# schody_v1.net
KiCad netlist of a schematic drawn in EAGLE
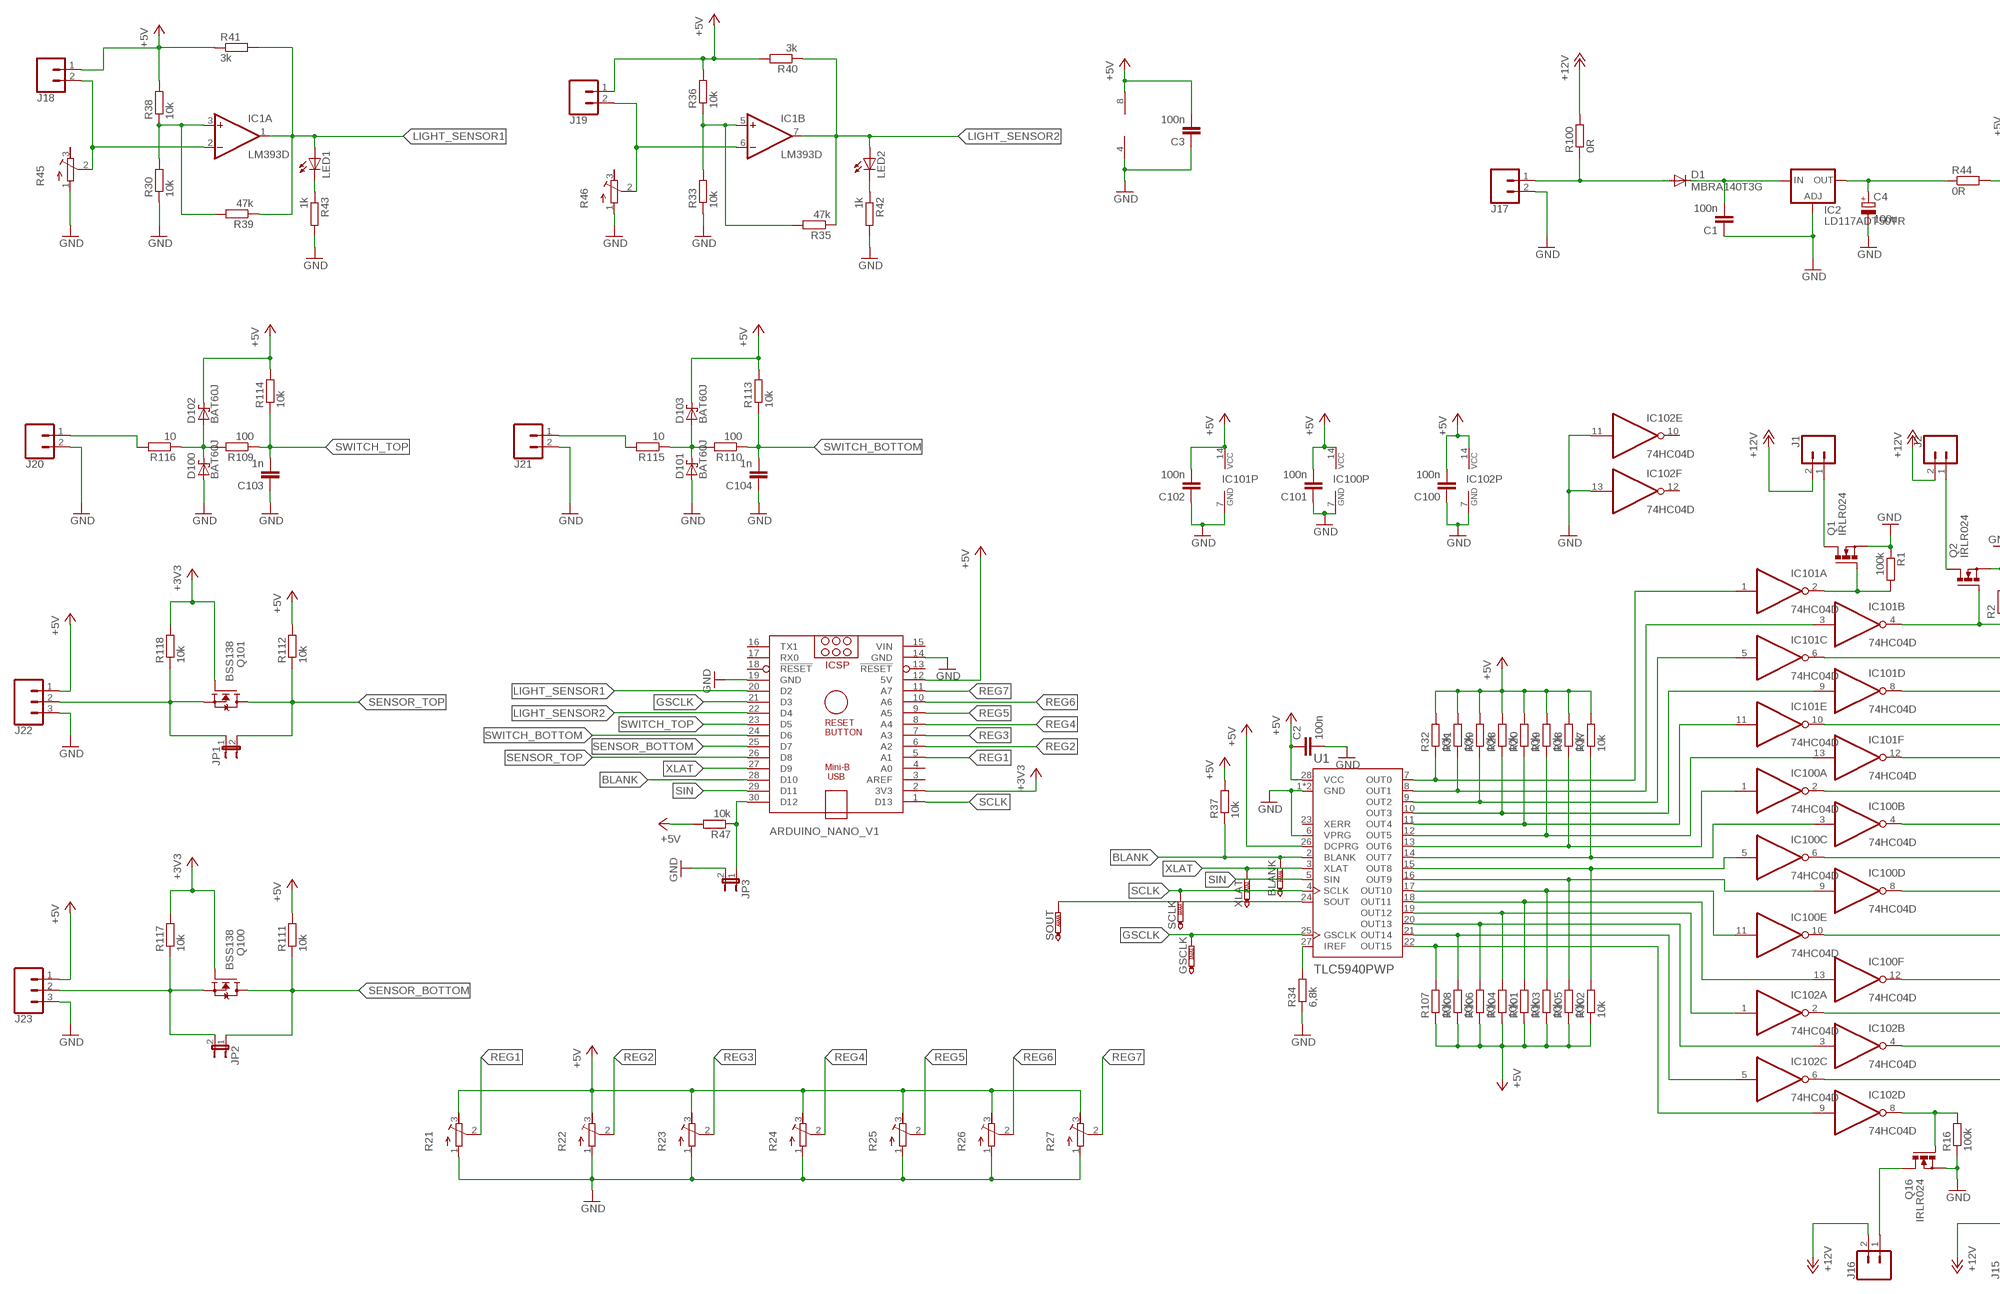
[diagram p0: schematic, sheet 1, part 1 of 2]
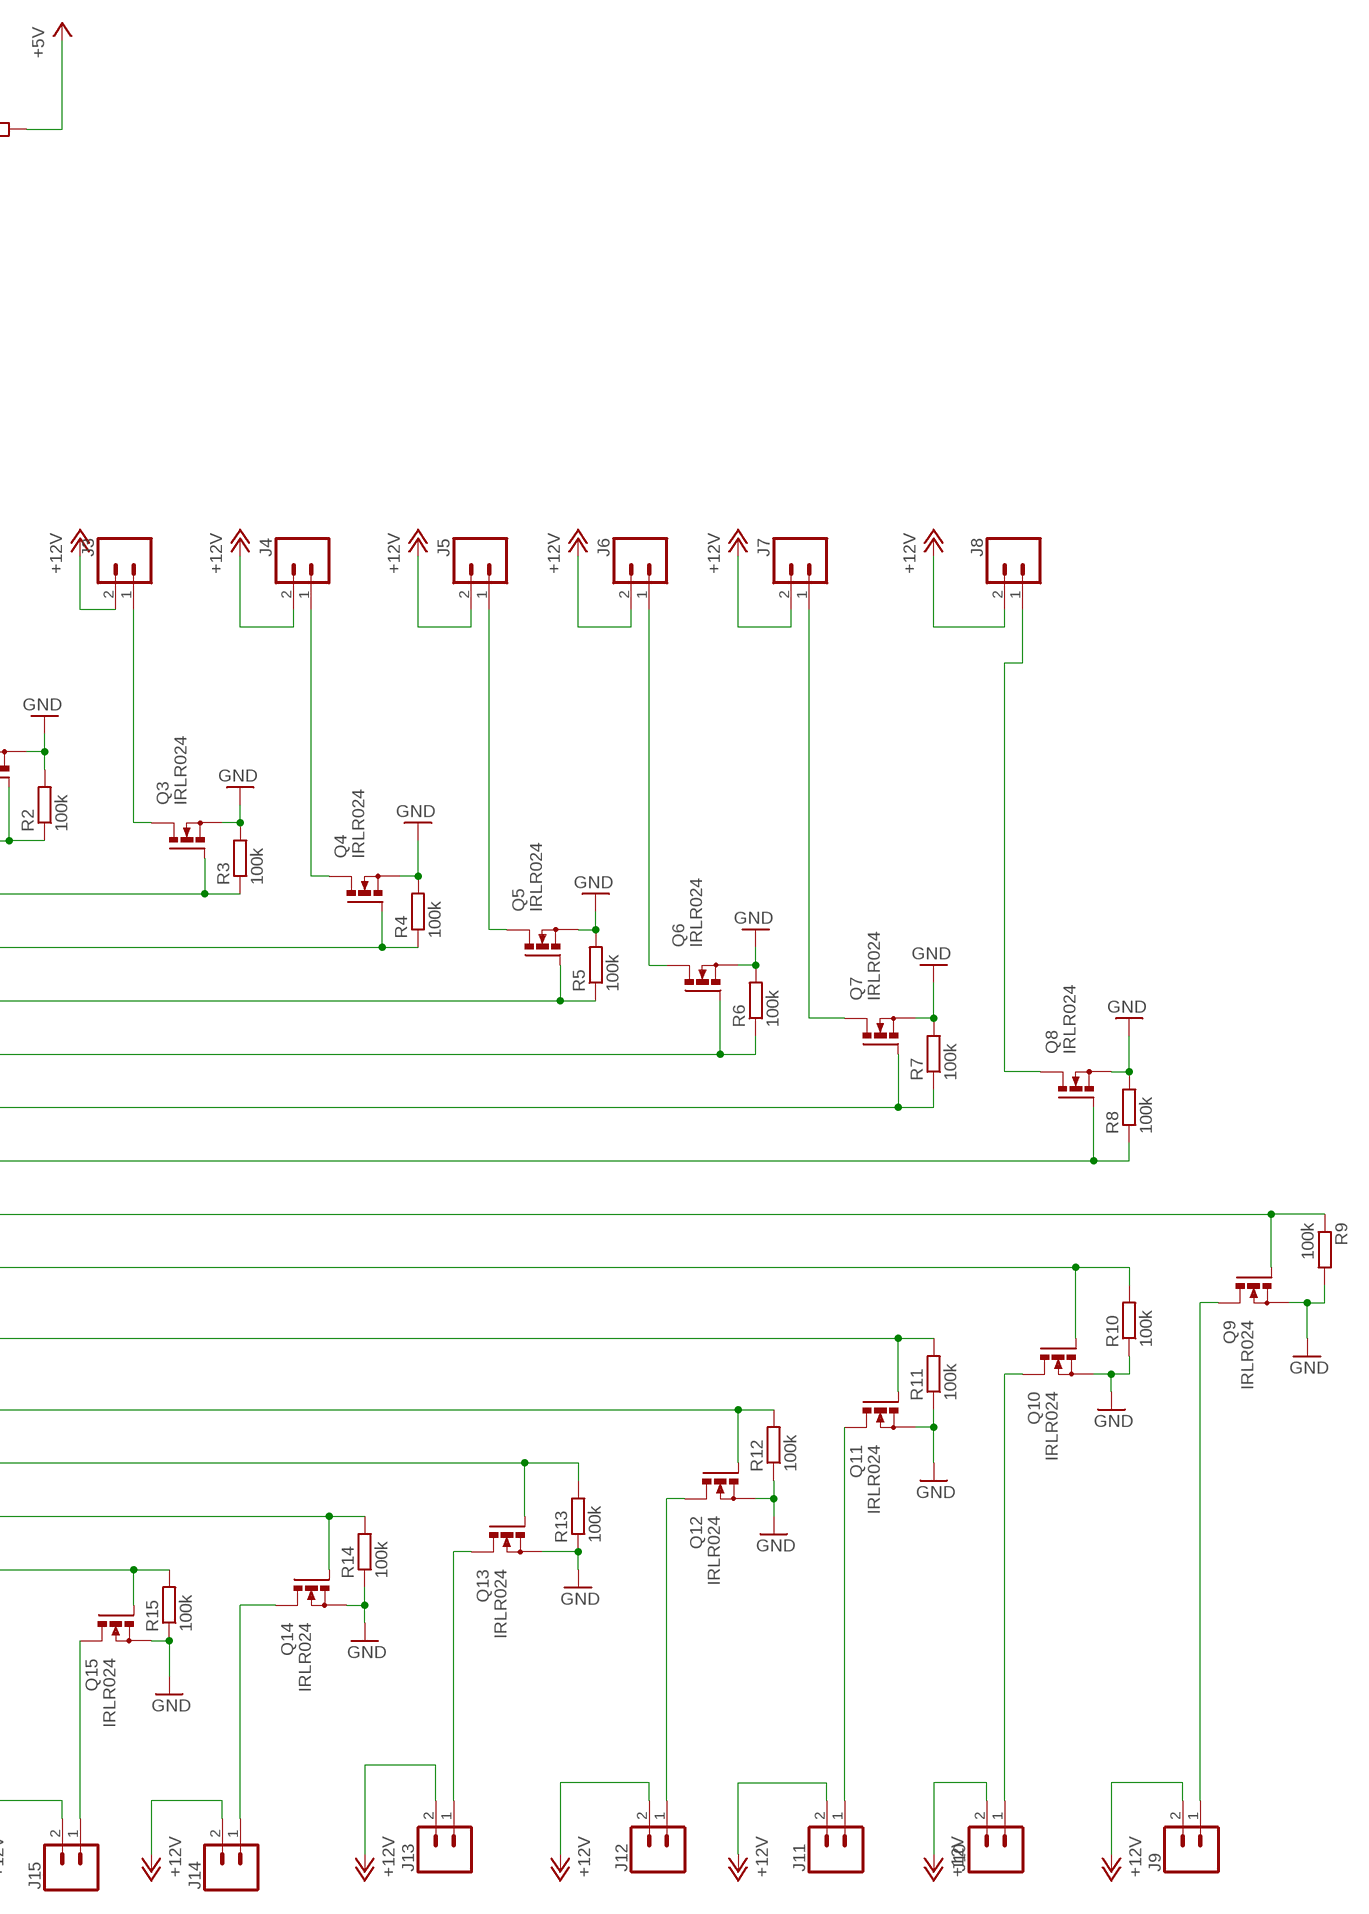
[diagram p1: schematic, sheet 1, part 2 of 2]

(export (version "E")
  (design (tool "Eeschema 10.0.6"))
  (components
    (comp (ref "ARDUINO_NANO_V1")
      (value "ARDUINO_NANO")
      (footprint "eagle-import:ARDUINO_NANO")
      (libsource (lib "eagle-import") (part "ARDUINO_NANO"))
    )
    (comp (ref "BLANK")
      (value "PTR1PAD1-13")
      (footprint "eagle-import:P1-13")
      (libsource (lib "eagle-import") (part "PTR1PAD1-13"))
    )
    (comp (ref "C1")
      (value "100n")
      (footprint "eagle-import:C0805K")
      (libsource (lib "eagle-import") (part "C-EUC0805K"))
    )
    (comp (ref "C2")
      (value "100n")
      (footprint "eagle-import:C0805K")
      (libsource (lib "eagle-import") (part "C-EUC0805K"))
    )
    (comp (ref "C3")
      (value "100n")
      (footprint "eagle-import:C0805K")
      (libsource (lib "eagle-import") (part "C-EUC0805K"))
    )
    (comp (ref "C4")
      (value "100u")
      (footprint "eagle-import:SMC_D")
      (libsource (lib "eagle-import") (part "CPOL-EUSMCD"))
    )
    (comp (ref "C100")
      (value "100n")
      (footprint "eagle-import:C0805K")
      (libsource (lib "eagle-import") (part "C-EUC0805K"))
    )
    (comp (ref "C101")
      (value "100n")
      (footprint "eagle-import:C0805K")
      (libsource (lib "eagle-import") (part "C-EUC0805K"))
    )
    (comp (ref "C102")
      (value "100n")
      (footprint "eagle-import:C0805K")
      (libsource (lib "eagle-import") (part "C-EUC0805K"))
    )
    (comp (ref "C103")
      (value "1n")
      (footprint "eagle-import:C0805K")
      (libsource (lib "eagle-import") (part "C-EUC0805K"))
    )
    (comp (ref "C104")
      (value "1n")
      (footprint "eagle-import:C0805K")
      (libsource (lib "eagle-import") (part "C-EUC0805K"))
    )
    (comp (ref "D1")
      (value "MBRA140T3G")
      (footprint "eagle-import:DO214BA")
      (libsource (lib "eagle-import") (part "DIODE-DO214BA"))
    )
    (comp (ref "D100")
      (value "BAT60J")
      (footprint "eagle-import:SOD323_ST")
      (libsource (lib "eagle-import") (part "BAT60J"))
    )
    (comp (ref "D101")
      (value "BAT60J")
      (footprint "eagle-import:SOD323_ST")
      (libsource (lib "eagle-import") (part "BAT60J"))
    )
    (comp (ref "D102")
      (value "BAT60J")
      (footprint "eagle-import:SOD323_ST")
      (libsource (lib "eagle-import") (part "BAT60J"))
    )
    (comp (ref "D103")
      (value "BAT60J")
      (footprint "eagle-import:SOD323_ST")
      (libsource (lib "eagle-import") (part "BAT60J"))
    )
    (comp (ref "GSCLK")
      (value "PTR1PAD1-13")
      (footprint "eagle-import:P1-13")
      (libsource (lib "eagle-import") (part "PTR1PAD1-13"))
    )
    (comp (ref "IC1")
      (value "LM393D")
      (footprint "eagle-import:SO08")
      (libsource (lib "eagle-import") (part "LM393D"))
    )
    (comp (ref "IC2")
      (value "LD117ADT50TR")
      (footprint "eagle-import:DPACK")
      (libsource (lib "eagle-import") (part "LD117A?DT50TR"))
    )
    (comp (ref "IC100")
      (value "74HC04D")
      (footprint "eagle-import:SO14")
      (libsource (lib "eagle-import") (part "7404DHC"))
    )
    (comp (ref "IC101")
      (value "74HC04D")
      (footprint "eagle-import:SO14")
      (libsource (lib "eagle-import") (part "7404DHC"))
    )
    (comp (ref "IC102")
      (value "74HC04D")
      (footprint "eagle-import:SO14")
      (libsource (lib "eagle-import") (part "7404DHC"))
    )
    (comp (ref "J1")
      (value "CONN_023.5MM")
      (footprint "eagle-import:SCREWTERMINAL-3.5MM-2")
      (libsource (lib "eagle-import") (part "CONN_023.5MM"))
    )
    (comp (ref "J2")
      (value "CONN_023.5MM")
      (footprint "eagle-import:SCREWTERMINAL-3.5MM-2")
      (libsource (lib "eagle-import") (part "CONN_023.5MM"))
    )
    (comp (ref "J3")
      (value "CONN_023.5MM")
      (footprint "eagle-import:SCREWTERMINAL-3.5MM-2")
      (libsource (lib "eagle-import") (part "CONN_023.5MM"))
    )
    (comp (ref "J4")
      (value "CONN_023.5MM")
      (footprint "eagle-import:SCREWTERMINAL-3.5MM-2")
      (libsource (lib "eagle-import") (part "CONN_023.5MM"))
    )
    (comp (ref "J5")
      (value "CONN_023.5MM")
      (footprint "eagle-import:SCREWTERMINAL-3.5MM-2")
      (libsource (lib "eagle-import") (part "CONN_023.5MM"))
    )
    (comp (ref "J6")
      (value "CONN_023.5MM")
      (footprint "eagle-import:SCREWTERMINAL-3.5MM-2")
      (libsource (lib "eagle-import") (part "CONN_023.5MM"))
    )
    (comp (ref "J7")
      (value "CONN_023.5MM")
      (footprint "eagle-import:SCREWTERMINAL-3.5MM-2")
      (libsource (lib "eagle-import") (part "CONN_023.5MM"))
    )
    (comp (ref "J8")
      (value "CONN_023.5MM")
      (footprint "eagle-import:SCREWTERMINAL-3.5MM-2")
      (libsource (lib "eagle-import") (part "CONN_023.5MM"))
    )
    (comp (ref "J9")
      (value "CONN_023.5MM")
      (footprint "eagle-import:SCREWTERMINAL-3.5MM-2")
      (libsource (lib "eagle-import") (part "CONN_023.5MM"))
    )
    (comp (ref "J10")
      (value "CONN_023.5MM")
      (footprint "eagle-import:SCREWTERMINAL-3.5MM-2")
      (libsource (lib "eagle-import") (part "CONN_023.5MM"))
    )
    (comp (ref "J11")
      (value "CONN_023.5MM")
      (footprint "eagle-import:SCREWTERMINAL-3.5MM-2")
      (libsource (lib "eagle-import") (part "CONN_023.5MM"))
    )
    (comp (ref "J12")
      (value "CONN_023.5MM")
      (footprint "eagle-import:SCREWTERMINAL-3.5MM-2")
      (libsource (lib "eagle-import") (part "CONN_023.5MM"))
    )
    (comp (ref "J13")
      (value "CONN_023.5MM")
      (footprint "eagle-import:SCREWTERMINAL-3.5MM-2")
      (libsource (lib "eagle-import") (part "CONN_023.5MM"))
    )
    (comp (ref "J14")
      (value "CONN_023.5MM")
      (footprint "eagle-import:SCREWTERMINAL-3.5MM-2")
      (libsource (lib "eagle-import") (part "CONN_023.5MM"))
    )
    (comp (ref "J15")
      (value "CONN_023.5MM")
      (footprint "eagle-import:SCREWTERMINAL-3.5MM-2")
      (libsource (lib "eagle-import") (part "CONN_023.5MM"))
    )
    (comp (ref "J16")
      (value "CONN_023.5MM")
      (footprint "eagle-import:SCREWTERMINAL-3.5MM-2")
      (libsource (lib "eagle-import") (part "CONN_023.5MM"))
    )
    (comp (ref "J17")
      (value "CONN_025MM")
      (footprint "eagle-import:SCREWTERMINAL-5MM-2")
      (libsource (lib "eagle-import") (part "CONN_025MM"))
    )
    (comp (ref "J18")
      (value "CONN_023.5MM")
      (footprint "eagle-import:SCREWTERMINAL-3.5MM-2")
      (libsource (lib "eagle-import") (part "CONN_023.5MM"))
    )
    (comp (ref "J19")
      (value "CONN_023.5MM")
      (footprint "eagle-import:SCREWTERMINAL-3.5MM-2")
      (libsource (lib "eagle-import") (part "CONN_023.5MM"))
    )
    (comp (ref "J20")
      (value "CONN_023.5MM")
      (footprint "eagle-import:SCREWTERMINAL-3.5MM-2")
      (libsource (lib "eagle-import") (part "CONN_023.5MM"))
    )
    (comp (ref "J21")
      (value "CONN_023.5MM")
      (footprint "eagle-import:SCREWTERMINAL-3.5MM-2")
      (libsource (lib "eagle-import") (part "CONN_023.5MM"))
    )
    (comp (ref "J22")
      (value "CONN_03SCREW")
      (footprint "eagle-import:SCREWTERMINAL-3.5MM-3")
      (libsource (lib "eagle-import") (part "CONN_03SCREW"))
    )
    (comp (ref "J23")
      (value "CONN_03SCREW")
      (footprint "eagle-import:SCREWTERMINAL-3.5MM-3")
      (libsource (lib "eagle-import") (part "CONN_03SCREW"))
    )
    (comp (ref "JP1")
      (value "JP1E")
      (footprint "eagle-import:JP1")
      (libsource (lib "eagle-import") (part "JP1E"))
    )
    (comp (ref "JP2")
      (value "JP1E")
      (footprint "eagle-import:JP1")
      (libsource (lib "eagle-import") (part "JP1E"))
    )
    (comp (ref "JP3")
      (value "JP1E")
      (footprint "eagle-import:JP1")
      (libsource (lib "eagle-import") (part "JP1E"))
    )
    (comp (ref "LED1")
      (value "LEDSML0805")
      (footprint "eagle-import:SML0805")
      (libsource (lib "eagle-import") (part "LEDSML0805"))
    )
    (comp (ref "LED2")
      (value "LEDSML0805")
      (footprint "eagle-import:SML0805")
      (libsource (lib "eagle-import") (part "LEDSML0805"))
    )
    (comp (ref "Q1")
      (value "IRLR024")
      (footprint "eagle-import:D-PAK_TO252AA")
      (libsource (lib "eagle-import") (part "IRLR024"))
    )
    (comp (ref "Q2")
      (value "IRLR024")
      (footprint "eagle-import:D-PAK_TO252AA")
      (libsource (lib "eagle-import") (part "IRLR024"))
    )
    (comp (ref "Q3")
      (value "IRLR024")
      (footprint "eagle-import:D-PAK_TO252AA")
      (libsource (lib "eagle-import") (part "IRLR024"))
    )
    (comp (ref "Q4")
      (value "IRLR024")
      (footprint "eagle-import:D-PAK_TO252AA")
      (libsource (lib "eagle-import") (part "IRLR024"))
    )
    (comp (ref "Q5")
      (value "IRLR024")
      (footprint "eagle-import:D-PAK_TO252AA")
      (libsource (lib "eagle-import") (part "IRLR024"))
    )
    (comp (ref "Q6")
      (value "IRLR024")
      (footprint "eagle-import:D-PAK_TO252AA")
      (libsource (lib "eagle-import") (part "IRLR024"))
    )
    (comp (ref "Q7")
      (value "IRLR024")
      (footprint "eagle-import:D-PAK_TO252AA")
      (libsource (lib "eagle-import") (part "IRLR024"))
    )
    (comp (ref "Q8")
      (value "IRLR024")
      (footprint "eagle-import:D-PAK_TO252AA")
      (libsource (lib "eagle-import") (part "IRLR024"))
    )
    (comp (ref "Q9")
      (value "IRLR024")
      (footprint "eagle-import:D-PAK_TO252AA")
      (libsource (lib "eagle-import") (part "IRLR024"))
    )
    (comp (ref "Q10")
      (value "IRLR024")
      (footprint "eagle-import:D-PAK_TO252AA")
      (libsource (lib "eagle-import") (part "IRLR024"))
    )
    (comp (ref "Q11")
      (value "IRLR024")
      (footprint "eagle-import:D-PAK_TO252AA")
      (libsource (lib "eagle-import") (part "IRLR024"))
    )
    (comp (ref "Q12")
      (value "IRLR024")
      (footprint "eagle-import:D-PAK_TO252AA")
      (libsource (lib "eagle-import") (part "IRLR024"))
    )
    (comp (ref "Q13")
      (value "IRLR024")
      (footprint "eagle-import:D-PAK_TO252AA")
      (libsource (lib "eagle-import") (part "IRLR024"))
    )
    (comp (ref "Q14")
      (value "IRLR024")
      (footprint "eagle-import:D-PAK_TO252AA")
      (libsource (lib "eagle-import") (part "IRLR024"))
    )
    (comp (ref "Q15")
      (value "IRLR024")
      (footprint "eagle-import:D-PAK_TO252AA")
      (libsource (lib "eagle-import") (part "IRLR024"))
    )
    (comp (ref "Q16")
      (value "IRLR024")
      (footprint "eagle-import:D-PAK_TO252AA")
      (libsource (lib "eagle-import") (part "IRLR024"))
    )
    (comp (ref "Q100")
      (value "BSS138")
      (footprint "eagle-import:SOT23")
      (fields (field (name "MF") "Fairchild"))
      (libsource (lib "eagle-import") (part "BSS138"))
    )
    (comp (ref "Q101")
      (value "BSS138")
      (footprint "eagle-import:SOT23")
      (fields (field (name "MF") "Fairchild"))
      (libsource (lib "eagle-import") (part "BSS138"))
    )
    (comp (ref "R1")
      (value "100k")
      (footprint "eagle-import:M0805")
      (libsource (lib "eagle-import") (part "resistor_348_R-EU_M0805"))
    )
    (comp (ref "R2")
      (value "100k")
      (footprint "eagle-import:M0805")
      (libsource (lib "eagle-import") (part "resistor_348_R-EU_M0805"))
    )
    (comp (ref "R3")
      (value "100k")
      (footprint "eagle-import:M0805")
      (libsource (lib "eagle-import") (part "resistor_348_R-EU_M0805"))
    )
    (comp (ref "R4")
      (value "100k")
      (footprint "eagle-import:M0805")
      (libsource (lib "eagle-import") (part "resistor_348_R-EU_M0805"))
    )
    (comp (ref "R5")
      (value "100k")
      (footprint "eagle-import:M0805")
      (libsource (lib "eagle-import") (part "resistor_348_R-EU_M0805"))
    )
    (comp (ref "R6")
      (value "100k")
      (footprint "eagle-import:M0805")
      (libsource (lib "eagle-import") (part "resistor_348_R-EU_M0805"))
    )
    (comp (ref "R7")
      (value "100k")
      (footprint "eagle-import:M0805")
      (libsource (lib "eagle-import") (part "resistor_348_R-EU_M0805"))
    )
    (comp (ref "R8")
      (value "100k")
      (footprint "eagle-import:M0805")
      (libsource (lib "eagle-import") (part "resistor_348_R-EU_M0805"))
    )
    (comp (ref "R9")
      (value "100k")
      (footprint "eagle-import:M0805")
      (libsource (lib "eagle-import") (part "resistor_348_R-EU_M0805"))
    )
    (comp (ref "R10")
      (value "100k")
      (footprint "eagle-import:M0805")
      (libsource (lib "eagle-import") (part "resistor_348_R-EU_M0805"))
    )
    (comp (ref "R11")
      (value "100k")
      (footprint "eagle-import:M0805")
      (libsource (lib "eagle-import") (part "resistor_348_R-EU_M0805"))
    )
    (comp (ref "R12")
      (value "100k")
      (footprint "eagle-import:M0805")
      (libsource (lib "eagle-import") (part "resistor_348_R-EU_M0805"))
    )
    (comp (ref "R13")
      (value "100k")
      (footprint "eagle-import:M0805")
      (libsource (lib "eagle-import") (part "resistor_348_R-EU_M0805"))
    )
    (comp (ref "R14")
      (value "100k")
      (footprint "eagle-import:M0805")
      (libsource (lib "eagle-import") (part "resistor_348_R-EU_M0805"))
    )
    (comp (ref "R15")
      (value "100k")
      (footprint "eagle-import:M0805")
      (libsource (lib "eagle-import") (part "resistor_348_R-EU_M0805"))
    )
    (comp (ref "R16")
      (value "100k")
      (footprint "eagle-import:M0805")
      (libsource (lib "eagle-import") (part "resistor_348_R-EU_M0805"))
    )
    (comp (ref "R17")
      (value "10k")
      (footprint "eagle-import:M0805")
      (libsource (lib "eagle-import") (part "resistor_348_R-EU_M0805"))
    )
    (comp (ref "R18")
      (value "10k")
      (footprint "eagle-import:M0805")
      (libsource (lib "eagle-import") (part "resistor_348_R-EU_M0805"))
    )
    (comp (ref "R19")
      (value "10k")
      (footprint "eagle-import:M0805")
      (libsource (lib "eagle-import") (part "resistor_348_R-EU_M0805"))
    )
    (comp (ref "R20")
      (value "10k")
      (footprint "eagle-import:M0805")
      (libsource (lib "eagle-import") (part "resistor_348_R-EU_M0805"))
    )
    (comp (ref "R21")
      (value "R-TRIMM64W")
      (footprint "eagle-import:RTRIM64W")
      (libsource (lib "eagle-import") (part "R-TRIMM64W"))
    )
    (comp (ref "R22")
      (value "R-TRIMM64W")
      (footprint "eagle-import:RTRIM64W")
      (libsource (lib "eagle-import") (part "R-TRIMM64W"))
    )
    (comp (ref "R23")
      (value "R-TRIMM64W")
      (footprint "eagle-import:RTRIM64W")
      (libsource (lib "eagle-import") (part "R-TRIMM64W"))
    )
    (comp (ref "R24")
      (value "R-TRIMM64W")
      (footprint "eagle-import:RTRIM64W")
      (libsource (lib "eagle-import") (part "R-TRIMM64W"))
    )
    (comp (ref "R25")
      (value "R-TRIMM64W")
      (footprint "eagle-import:RTRIM64W")
      (libsource (lib "eagle-import") (part "R-TRIMM64W"))
    )
    (comp (ref "R26")
      (value "R-TRIMM64W")
      (footprint "eagle-import:RTRIM64W")
      (libsource (lib "eagle-import") (part "R-TRIMM64W"))
    )
    (comp (ref "R27")
      (value "R-TRIMM64W")
      (footprint "eagle-import:RTRIM64W")
      (libsource (lib "eagle-import") (part "R-TRIMM64W"))
    )
    (comp (ref "R28")
      (value "10k")
      (footprint "eagle-import:M0805")
      (libsource (lib "eagle-import") (part "resistor_348_R-EU_M0805"))
    )
    (comp (ref "R29")
      (value "10k")
      (footprint "eagle-import:M0805")
      (libsource (lib "eagle-import") (part "resistor_348_R-EU_M0805"))
    )
    (comp (ref "R30")
      (value "10k")
      (footprint "eagle-import:M0805")
      (libsource (lib "eagle-import") (part "resistor_348_R-EU_M0805"))
    )
    (comp (ref "R31")
      (value "10k")
      (footprint "eagle-import:M0805")
      (libsource (lib "eagle-import") (part "resistor_348_R-EU_M0805"))
    )
    (comp (ref "R32")
      (value "10k")
      (footprint "eagle-import:M0805")
      (libsource (lib "eagle-import") (part "resistor_348_R-EU_M0805"))
    )
    (comp (ref "R33")
      (value "10k")
      (footprint "eagle-import:M0805")
      (libsource (lib "eagle-import") (part "resistor_348_R-EU_M0805"))
    )
    (comp (ref "R34")
      (value "6,8k")
      (footprint "eagle-import:M0805")
      (libsource (lib "eagle-import") (part "resistor_348_R-EU_M0805"))
    )
    (comp (ref "R35")
      (value "47k")
      (footprint "eagle-import:M0805")
      (libsource (lib "eagle-import") (part "resistor_348_R-EU_M0805"))
    )
    (comp (ref "R36")
      (value "10k")
      (footprint "eagle-import:M0805")
      (libsource (lib "eagle-import") (part "resistor_348_R-EU_M0805"))
    )
    (comp (ref "R37")
      (value "10k")
      (footprint "eagle-import:M0805")
      (libsource (lib "eagle-import") (part "resistor_348_R-EU_M0805"))
    )
    (comp (ref "R38")
      (value "10k")
      (footprint "eagle-import:M0805")
      (libsource (lib "eagle-import") (part "resistor_348_R-EU_M0805"))
    )
    (comp (ref "R39")
      (value "47k")
      (footprint "eagle-import:M0805")
      (libsource (lib "eagle-import") (part "resistor_348_R-EU_M0805"))
    )
    (comp (ref "R40")
      (value "3k")
      (footprint "eagle-import:M0805")
      (libsource (lib "eagle-import") (part "resistor_348_R-EU_M0805"))
    )
    (comp (ref "R41")
      (value "3k")
      (footprint "eagle-import:M0805")
      (libsource (lib "eagle-import") (part "resistor_348_R-EU_M0805"))
    )
    (comp (ref "R42")
      (value "1k")
      (footprint "eagle-import:M0805")
      (libsource (lib "eagle-import") (part "resistor_348_R-EU_M0805"))
    )
    (comp (ref "R43")
      (value "1k")
      (footprint "eagle-import:M0805")
      (libsource (lib "eagle-import") (part "resistor_348_R-EU_M0805"))
    )
    (comp (ref "R44")
      (value "0R")
      (footprint "eagle-import:M1206")
      (libsource (lib "eagle-import") (part "R-EU_M1206"))
    )
    (comp (ref "R45")
      (value "R-TRIMM64W")
      (footprint "eagle-import:RTRIM64W")
      (libsource (lib "eagle-import") (part "R-TRIMM64W"))
    )
    (comp (ref "R46")
      (value "R-TRIMM64W")
      (footprint "eagle-import:RTRIM64W")
      (libsource (lib "eagle-import") (part "R-TRIMM64W"))
    )
    (comp (ref "R47")
      (value "10k")
      (footprint "eagle-import:M0805")
      (libsource (lib "eagle-import") (part "resistor_348_R-EU_M0805"))
    )
    (comp (ref "R100")
      (value "0R")
      (footprint "eagle-import:R2512")
      (libsource (lib "eagle-import") (part "resistor_348_R-EU_R2512"))
    )
    (comp (ref "R101")
      (value "10k")
      (footprint "eagle-import:M0805")
      (libsource (lib "eagle-import") (part "resistor_348_R-EU_M0805"))
    )
    (comp (ref "R102")
      (value "10k")
      (footprint "eagle-import:M0805")
      (libsource (lib "eagle-import") (part "resistor_348_R-EU_M0805"))
    )
    (comp (ref "R103")
      (value "10k")
      (footprint "eagle-import:M0805")
      (libsource (lib "eagle-import") (part "resistor_348_R-EU_M0805"))
    )
    (comp (ref "R104")
      (value "10k")
      (footprint "eagle-import:M0805")
      (libsource (lib "eagle-import") (part "resistor_348_R-EU_M0805"))
    )
    (comp (ref "R105")
      (value "10k")
      (footprint "eagle-import:M0805")
      (libsource (lib "eagle-import") (part "resistor_348_R-EU_M0805"))
    )
    (comp (ref "R106")
      (value "10k")
      (footprint "eagle-import:M0805")
      (libsource (lib "eagle-import") (part "resistor_348_R-EU_M0805"))
    )
    (comp (ref "R107")
      (value "10k")
      (footprint "eagle-import:M0805")
      (libsource (lib "eagle-import") (part "resistor_348_R-EU_M0805"))
    )
    (comp (ref "R108")
      (value "10k")
      (footprint "eagle-import:M0805")
      (libsource (lib "eagle-import") (part "resistor_348_R-EU_M0805"))
    )
    (comp (ref "R109")
      (value "100")
      (footprint "eagle-import:M0805")
      (libsource (lib "eagle-import") (part "resistor_348_R-EU_M0805"))
    )
    (comp (ref "R110")
      (value "100")
      (footprint "eagle-import:M0805")
      (libsource (lib "eagle-import") (part "resistor_348_R-EU_M0805"))
    )
    (comp (ref "R111")
      (value "10k")
      (footprint "eagle-import:M0805")
      (libsource (lib "eagle-import") (part "resistor_348_R-EU_M0805"))
    )
    (comp (ref "R112")
      (value "10k")
      (footprint "eagle-import:M0805")
      (libsource (lib "eagle-import") (part "resistor_348_R-EU_M0805"))
    )
    (comp (ref "R113")
      (value "10k")
      (footprint "eagle-import:M0805")
      (libsource (lib "eagle-import") (part "resistor_348_R-EU_M0805"))
    )
    (comp (ref "R114")
      (value "10k")
      (footprint "eagle-import:M0805")
      (libsource (lib "eagle-import") (part "resistor_348_R-EU_M0805"))
    )
    (comp (ref "R115")
      (value "10")
      (footprint "eagle-import:M0805")
      (libsource (lib "eagle-import") (part "resistor_348_R-EU_M0805"))
    )
    (comp (ref "R116")
      (value "10")
      (footprint "eagle-import:M0805")
      (libsource (lib "eagle-import") (part "resistor_348_R-EU_M0805"))
    )
    (comp (ref "R117")
      (value "10k")
      (footprint "eagle-import:M0805")
      (libsource (lib "eagle-import") (part "resistor_348_R-EU_M0805"))
    )
    (comp (ref "R118")
      (value "10k")
      (footprint "eagle-import:M0805")
      (libsource (lib "eagle-import") (part "resistor_348_R-EU_M0805"))
    )
    (comp (ref "SCLK")
      (value "PTR1PAD1-13")
      (footprint "eagle-import:P1-13")
      (libsource (lib "eagle-import") (part "PTR1PAD1-13"))
    )
    (comp (ref "SOUT")
      (value "PTR1PAD1-13")
      (footprint "eagle-import:P1-13")
      (libsource (lib "eagle-import") (part "PTR1PAD1-13"))
    )
    (comp (ref "U1")
      (value "TLC5940PWP")
      (footprint "eagle-import:HTSSOP28PWP")
      (libsource (lib "eagle-import") (part "TLC5940PWP"))
    )
    (comp (ref "XLAT")
      (value "PTR1PAD1-13")
      (footprint "eagle-import:P1-13")
      (libsource (lib "eagle-import") (part "PTR1PAD1-13"))
    )
  )
  (nets
    (net (code "1") (name "+3V3") (class "Default")
      (node (ref "ARDUINO_NANO_V1") (pin "2") (pinfunction "3V3_2") (pintype "output"))
      (node (ref "Q100") (pin "1") (pinfunction "G_1") (pintype "passive"))
      (node (ref "Q101") (pin "1") (pinfunction "G_1") (pintype "passive"))
      (node (ref "R117") (pin "2") (pinfunction "2_2") (pintype "passive"))
      (node (ref "R118") (pin "2") (pinfunction "2_2") (pintype "passive"))
    )
    (net (code "2") (name "+5V") (class "Default")
      (node (ref "ARDUINO_NANO_V1") (pin "12") (pinfunction "5V_12") (pintype "power_in"))
      (node (ref "C100") (pin "2") (pinfunction "2_2") (pintype "passive"))
      (node (ref "C101") (pin "2") (pinfunction "2_2") (pintype "passive"))
      (node (ref "C102") (pin "2") (pinfunction "2_2") (pintype "passive"))
      (node (ref "C2") (pin "1") (pinfunction "1_1") (pintype "passive"))
      (node (ref "C3") (pin "2") (pinfunction "2_2") (pintype "passive"))
      (node (ref "D102") (pin "C") (pinfunction "C_C") (pintype "passive"))
      (node (ref "D103") (pin "C") (pinfunction "C_C") (pintype "passive"))
      (node (ref "IC1") (pin "8") (pinfunction "V+_8") (pintype "power_in"))
      (node (ref "IC100") (pin "14") (pinfunction "VCC_14") (pintype "power_in"))
      (node (ref "IC101") (pin "14") (pinfunction "VCC_14") (pintype "power_in"))
      (node (ref "IC102") (pin "14") (pinfunction "VCC_14") (pintype "power_in"))
      (node (ref "J18") (pin "1") (pinfunction "1_1") (pintype "passive"))
      (node (ref "J19") (pin "1") (pinfunction "1_1") (pintype "passive"))
      (node (ref "J22") (pin "1") (pinfunction "1_1") (pintype "passive"))
      (node (ref "J23") (pin "1") (pinfunction "1_1") (pintype "passive"))
      (node (ref "R101") (pin "1") (pinfunction "1_1") (pintype "passive"))
      (node (ref "R102") (pin "1") (pinfunction "1_1") (pintype "passive"))
      (node (ref "R103") (pin "1") (pinfunction "1_1") (pintype "passive"))
      (node (ref "R104") (pin "1") (pinfunction "1_1") (pintype "passive"))
      (node (ref "R105") (pin "1") (pinfunction "1_1") (pintype "passive"))
      (node (ref "R106") (pin "1") (pinfunction "1_1") (pintype "passive"))
      (node (ref "R107") (pin "1") (pinfunction "1_1") (pintype "passive"))
      (node (ref "R108") (pin "1") (pinfunction "1_1") (pintype "passive"))
      (node (ref "R111") (pin "2") (pinfunction "2_2") (pintype "passive"))
      (node (ref "R112") (pin "2") (pinfunction "2_2") (pintype "passive"))
      (node (ref "R113") (pin "2") (pinfunction "2_2") (pintype "passive"))
      (node (ref "R114") (pin "2") (pinfunction "2_2") (pintype "passive"))
      (node (ref "R17") (pin "2") (pinfunction "2_2") (pintype "passive"))
      (node (ref "R18") (pin "2") (pinfunction "2_2") (pintype "passive"))
      (node (ref "R19") (pin "2") (pinfunction "2_2") (pintype "passive"))
      (node (ref "R20") (pin "2") (pinfunction "2_2") (pintype "passive"))
      (node (ref "R21") (pin "3") (pinfunction "E_3") (pintype "passive"))
      (node (ref "R22") (pin "3") (pinfunction "E_3") (pintype "passive"))
      (node (ref "R23") (pin "3") (pinfunction "E_3") (pintype "passive"))
      (node (ref "R24") (pin "3") (pinfunction "E_3") (pintype "passive"))
      (node (ref "R25") (pin "3") (pinfunction "E_3") (pintype "passive"))
      (node (ref "R26") (pin "3") (pinfunction "E_3") (pintype "passive"))
      (node (ref "R27") (pin "3") (pinfunction "E_3") (pintype "passive"))
      (node (ref "R28") (pin "2") (pinfunction "2_2") (pintype "passive"))
      (node (ref "R29") (pin "2") (pinfunction "2_2") (pintype "passive"))
      (node (ref "R31") (pin "2") (pinfunction "2_2") (pintype "passive"))
      (node (ref "R32") (pin "2") (pinfunction "2_2") (pintype "passive"))
      (node (ref "R36") (pin "2") (pinfunction "2_2") (pintype "passive"))
      (node (ref "R37") (pin "2") (pinfunction "2_2") (pintype "passive"))
      (node (ref "R38") (pin "2") (pinfunction "2_2") (pintype "passive"))
      (node (ref "R40") (pin "2") (pinfunction "2_2") (pintype "passive"))
      (node (ref "R41") (pin "1") (pinfunction "1_1") (pintype "passive"))
      (node (ref "R44") (pin "2") (pinfunction "2_2") (pintype "passive"))
      (node (ref "R47") (pin "2") (pinfunction "2_2") (pintype "passive"))
      (node (ref "U1") (pin "26") (pinfunction "DCPRG_26") (pintype "input"))
      (node (ref "U1") (pin "28") (pinfunction "VCC_28") (pintype "power_in"))
    )
    (net (code "3") (name "+12V") (class "Default")
      (node (ref "J1") (pin "2") (pinfunction "2_2") (pintype "passive"))
      (node (ref "J10") (pin "2") (pinfunction "2_2") (pintype "passive"))
      (node (ref "J11") (pin "2") (pinfunction "2_2") (pintype "passive"))
      (node (ref "J12") (pin "2") (pinfunction "2_2") (pintype "passive"))
      (node (ref "J13") (pin "2") (pinfunction "2_2") (pintype "passive"))
      (node (ref "J14") (pin "2") (pinfunction "2_2") (pintype "passive"))
      (node (ref "J15") (pin "2") (pinfunction "2_2") (pintype "passive"))
      (node (ref "J16") (pin "2") (pinfunction "2_2") (pintype "passive"))
      (node (ref "J2") (pin "2") (pinfunction "2_2") (pintype "passive"))
      (node (ref "J3") (pin "2") (pinfunction "2_2") (pintype "passive"))
      (node (ref "J4") (pin "2") (pinfunction "2_2") (pintype "passive"))
      (node (ref "J5") (pin "2") (pinfunction "2_2") (pintype "passive"))
      (node (ref "J6") (pin "2") (pinfunction "2_2") (pintype "passive"))
      (node (ref "J7") (pin "2") (pinfunction "2_2") (pintype "passive"))
      (node (ref "J8") (pin "2") (pinfunction "2_2") (pintype "passive"))
      (node (ref "J9") (pin "2") (pinfunction "2_2") (pintype "passive"))
      (node (ref "R100") (pin "2") (pinfunction "2_2") (pintype "passive"))
    )
    (net (code "4") (name "/VIN") (class "Default")
      (node (ref "ARDUINO_NANO_V1") (pin "15") (pinfunction "VIN_15") (pintype "power_in"))
    )
    (net (code "5") (name "BLANK") (class "Default")
      (node (ref "ARDUINO_NANO_V1") (pin "28") (pinfunction "D10_28") (pintype "bidirectional"))
      (node (ref "BLANK") (pin "TP") (pinfunction "TP_TP") (pintype "input"))
      (node (ref "R37") (pin "1") (pinfunction "1_1") (pintype "passive"))
      (node (ref "U1") (pin "2") (pinfunction "BLANK_2") (pintype "input"))
    )
    (net (code "6") (name "GND") (class "Default")
      (node (ref "ARDUINO_NANO_V1") (pin "14") (pinfunction "GND_14") (pintype "power_in"))
      (node (ref "ARDUINO_NANO_V1") (pin "19") (pinfunction "GND_19") (pintype "power_in"))
      (node (ref "C1") (pin "1") (pinfunction "1_1") (pintype "passive"))
      (node (ref "C100") (pin "1") (pinfunction "1_1") (pintype "passive"))
      (node (ref "C101") (pin "1") (pinfunction "1_1") (pintype "passive"))
      (node (ref "C102") (pin "1") (pinfunction "1_1") (pintype "passive"))
      (node (ref "C103") (pin "1") (pinfunction "1_1") (pintype "passive"))
      (node (ref "C104") (pin "1") (pinfunction "1_1") (pintype "passive"))
      (node (ref "C2") (pin "2") (pinfunction "2_2") (pintype "passive"))
      (node (ref "C3") (pin "1") (pinfunction "1_1") (pintype "passive"))
      (node (ref "C4") (pin "-") (pinfunction "-_-") (pintype "passive"))
      (node (ref "D100") (pin "A") (pinfunction "A_A") (pintype "passive"))
      (node (ref "D101") (pin "A") (pinfunction "A_A") (pintype "passive"))
      (node (ref "IC1") (pin "4") (pinfunction "V-_4") (pintype "power_in"))
      (node (ref "IC100") (pin "7") (pinfunction "GND_7") (pintype "power_in"))
      (node (ref "IC101") (pin "7") (pinfunction "GND_7") (pintype "power_in"))
      (node (ref "IC102") (pin "11") (pinfunction "I_11") (pintype "input"))
      (node (ref "IC102") (pin "13") (pinfunction "I_13") (pintype "input"))
      (node (ref "IC102") (pin "7") (pinfunction "GND_7") (pintype "power_in"))
      (node (ref "IC2") (pin "1") (pinfunction "ADJ_1") (pintype "input"))
      (node (ref "J17") (pin "2") (pinfunction "2_2") (pintype "passive"))
      (node (ref "J20") (pin "2") (pinfunction "2_2") (pintype "passive"))
      (node (ref "J21") (pin "2") (pinfunction "2_2") (pintype "passive"))
      (node (ref "J22") (pin "3") (pinfunction "3_3") (pintype "passive"))
      (node (ref "J23") (pin "3") (pinfunction "3_3") (pintype "passive"))
      (node (ref "JP3") (pin "2") (pinfunction "2_2") (pintype "passive"))
      (node (ref "Q1") (pin "3") (pinfunction "SOURCE_3") (pintype "bidirectional"))
      (node (ref "Q10") (pin "3") (pinfunction "SOURCE_3") (pintype "bidirectional"))
      (node (ref "Q11") (pin "3") (pinfunction "SOURCE_3") (pintype "bidirectional"))
      (node (ref "Q12") (pin "3") (pinfunction "SOURCE_3") (pintype "bidirectional"))
      (node (ref "Q13") (pin "3") (pinfunction "SOURCE_3") (pintype "bidirectional"))
      (node (ref "Q14") (pin "3") (pinfunction "SOURCE_3") (pintype "bidirectional"))
      (node (ref "Q15") (pin "3") (pinfunction "SOURCE_3") (pintype "bidirectional"))
      (node (ref "Q16") (pin "3") (pinfunction "SOURCE_3") (pintype "bidirectional"))
      (node (ref "Q2") (pin "3") (pinfunction "SOURCE_3") (pintype "bidirectional"))
      (node (ref "Q3") (pin "3") (pinfunction "SOURCE_3") (pintype "bidirectional"))
      (node (ref "Q4") (pin "3") (pinfunction "SOURCE_3") (pintype "bidirectional"))
      (node (ref "Q5") (pin "3") (pinfunction "SOURCE_3") (pintype "bidirectional"))
      (node (ref "Q6") (pin "3") (pinfunction "SOURCE_3") (pintype "bidirectional"))
      (node (ref "Q7") (pin "3") (pinfunction "SOURCE_3") (pintype "bidirectional"))
      (node (ref "Q8") (pin "3") (pinfunction "SOURCE_3") (pintype "bidirectional"))
      (node (ref "Q9") (pin "3") (pinfunction "SOURCE_3") (pintype "bidirectional"))
      (node (ref "R1") (pin "1") (pinfunction "1_1") (pintype "passive"))
      (node (ref "R10") (pin "1") (pinfunction "1_1") (pintype "passive"))
      (node (ref "R11") (pin "1") (pinfunction "1_1") (pintype "passive"))
      (node (ref "R12") (pin "1") (pinfunction "1_1") (pintype "passive"))
      (node (ref "R13") (pin "1") (pinfunction "1_1") (pintype "passive"))
      (node (ref "R14") (pin "1") (pinfunction "1_1") (pintype "passive"))
      (node (ref "R15") (pin "1") (pinfunction "1_1") (pintype "passive"))
      (node (ref "R16") (pin "1") (pinfunction "1_1") (pintype "passive"))
      (node (ref "R2") (pin "2") (pinfunction "2_2") (pintype "passive"))
      (node (ref "R21") (pin "1") (pinfunction "A_1") (pintype "passive"))
      (node (ref "R22") (pin "1") (pinfunction "A_1") (pintype "passive"))
      (node (ref "R23") (pin "1") (pinfunction "A_1") (pintype "passive"))
      (node (ref "R24") (pin "1") (pinfunction "A_1") (pintype "passive"))
      (node (ref "R25") (pin "1") (pinfunction "A_1") (pintype "passive"))
      (node (ref "R26") (pin "1") (pinfunction "A_1") (pintype "passive"))
      (node (ref "R27") (pin "1") (pinfunction "A_1") (pintype "passive"))
      (node (ref "R3") (pin "2") (pinfunction "2_2") (pintype "passive"))
      (node (ref "R30") (pin "1") (pinfunction "1_1") (pintype "passive"))
      (node (ref "R33") (pin "1") (pinfunction "1_1") (pintype "passive"))
      (node (ref "R34") (pin "1") (pinfunction "1_1") (pintype "passive"))
      (node (ref "R4") (pin "2") (pinfunction "2_2") (pintype "passive"))
      (node (ref "R42") (pin "2") (pinfunction "2_2") (pintype "passive"))
      (node (ref "R43") (pin "2") (pinfunction "2_2") (pintype "passive"))
      (node (ref "R45") (pin "1") (pinfunction "A_1") (pintype "passive"))
      (node (ref "R46") (pin "1") (pinfunction "A_1") (pintype "passive"))
      (node (ref "R5") (pin "2") (pinfunction "2_2") (pintype "passive"))
      (node (ref "R6") (pin "2") (pinfunction "2_2") (pintype "passive"))
      (node (ref "R7") (pin "2") (pinfunction "2_2") (pintype "passive"))
      (node (ref "R8") (pin "2") (pinfunction "2_2") (pintype "passive"))
      (node (ref "R9") (pin "2") (pinfunction "2_2") (pintype "passive"))
      (node (ref "U1") (pin "1") (pinfunction "GND_1") (pintype "power_in"))
      (node (ref "U1") (pin "6") (pinfunction "VPRG_6") (pintype "input"))
      (node (ref "U1") (pin "EXP") (pinfunction "GND_EXP") (pintype "power_in"))
    )
    (net (code "7") (name "GSCLK") (class "Default")
      (node (ref "ARDUINO_NANO_V1") (pin "21") (pinfunction "D3_21") (pintype "bidirectional"))
      (node (ref "GSCLK") (pin "TP") (pinfunction "TP_TP") (pintype "input"))
      (node (ref "U1") (pin "25") (pinfunction "GSCLK_25") (pintype "input"))
    )
    (net (code "8") (name "LIGHT_SENSOR1") (class "Default")
      (node (ref "ARDUINO_NANO_V1") (pin "20") (pinfunction "D2_20") (pintype "bidirectional"))
      (node (ref "IC1") (pin "1") (pinfunction "OUT_1") (pintype "output"))
      (node (ref "LED1") (pin "A") (pinfunction "A_A") (pintype "passive"))
      (node (ref "R39") (pin "1") (pinfunction "1_1") (pintype "passive"))
      (node (ref "R41") (pin "2") (pinfunction "2_2") (pintype "passive"))
    )
    (net (code "9") (name "LIGHT_SENSOR2") (class "Default")
      (node (ref "ARDUINO_NANO_V1") (pin "22") (pinfunction "D4_22") (pintype "bidirectional"))
      (node (ref "IC1") (pin "7") (pinfunction "OUT_7") (pintype "output"))
      (node (ref "LED2") (pin "A") (pinfunction "A_A") (pintype "passive"))
      (node (ref "R35") (pin "1") (pinfunction "1_1") (pintype "passive"))
      (node (ref "R40") (pin "1") (pinfunction "1_1") (pintype "passive"))
    )
    (net (code "10") (name "Net-(ARDUINO_NANO_V1-D12)") (class "Default")
      (node (ref "ARDUINO_NANO_V1") (pin "30") (pinfunction "D12_30") (pintype "bidirectional"))
      (node (ref "JP3") (pin "1") (pinfunction "1_1") (pintype "passive"))
      (node (ref "R47") (pin "1") (pinfunction "1_1") (pintype "passive"))
    )
    (net (code "11") (name "Net-(D1-PadA)") (class "Default")
      (node (ref "D1") (pin "A") (pinfunction "A_A") (pintype "passive"))
      (node (ref "J17") (pin "1") (pinfunction "1_1") (pintype "passive"))
      (node (ref "R100") (pin "1") (pinfunction "1_1") (pintype "passive"))
    )
    (net (code "12") (name "Net-(D100-PadC)") (class "Default")
      (node (ref "D100") (pin "C") (pinfunction "C_C") (pintype "passive"))
      (node (ref "D102") (pin "A") (pinfunction "A_A") (pintype "passive"))
      (node (ref "R109") (pin "2") (pinfunction "2_2") (pintype "passive"))
      (node (ref "R116") (pin "1") (pinfunction "1_1") (pintype "passive"))
    )
    (net (code "13") (name "Net-(D101-PadC)") (class "Default")
      (node (ref "D101") (pin "C") (pinfunction "C_C") (pintype "passive"))
      (node (ref "D103") (pin "A") (pinfunction "A_A") (pintype "passive"))
      (node (ref "R110") (pin "2") (pinfunction "2_2") (pintype "passive"))
      (node (ref "R115") (pin "1") (pinfunction "1_1") (pintype "passive"))
    )
    (net (code "14") (name "Net-(IC1A-+IN)") (class "Default")
      (node (ref "IC1") (pin "3") (pinfunction "+IN_3") (pintype "input"))
      (node (ref "R30") (pin "2") (pinfunction "2_2") (pintype "passive"))
      (node (ref "R38") (pin "1") (pinfunction "1_1") (pintype "passive"))
      (node (ref "R39") (pin "2") (pinfunction "2_2") (pintype "passive"))
    )
    (net (code "15") (name "Net-(IC1A--IN)") (class "Default")
      (node (ref "IC1") (pin "2") (pinfunction "-IN_2") (pintype "input"))
      (node (ref "J18") (pin "2") (pinfunction "2_2") (pintype "passive"))
      (node (ref "R45") (pin "2") (pinfunction "S_2") (pintype "passive"))
    )
    (net (code "16") (name "Net-(IC1B-+IN)") (class "Default")
      (node (ref "IC1") (pin "5") (pinfunction "+IN_5") (pintype "input"))
      (node (ref "R33") (pin "2") (pinfunction "2_2") (pintype "passive"))
      (node (ref "R35") (pin "2") (pinfunction "2_2") (pintype "passive"))
      (node (ref "R36") (pin "1") (pinfunction "1_1") (pintype "passive"))
    )
    (net (code "17") (name "Net-(IC1B--IN)") (class "Default")
      (node (ref "IC1") (pin "6") (pinfunction "-IN_6") (pintype "input"))
      (node (ref "J19") (pin "2") (pinfunction "2_2") (pintype "passive"))
      (node (ref "R46") (pin "2") (pinfunction "S_2") (pintype "passive"))
    )
    (net (code "18") (name "Net-(IC2-IN)") (class "Default")
      (node (ref "C1") (pin "2") (pinfunction "2_2") (pintype "passive"))
      (node (ref "D1") (pin "C") (pinfunction "C_C") (pintype "passive"))
      (node (ref "IC2") (pin "3") (pinfunction "IN_3") (pintype "input"))
    )
    (net (code "19") (name "Net-(IC2-OUT)") (class "Default")
      (node (ref "C4") (pin "+") (pinfunction "+_+") (pintype "passive"))
      (node (ref "IC2") (pin "4") (pinfunction "OUT_4") (pintype "passive"))
      (node (ref "R44") (pin "1") (pinfunction "1_1") (pintype "passive"))
    )
    (net (code "20") (name "Net-(IC100A-I)") (class "Default")
      (node (ref "IC100") (pin "1") (pinfunction "I_1") (pintype "input"))
      (node (ref "R18") (pin "1") (pinfunction "1_1") (pintype "passive"))
      (node (ref "U1") (pin "13") (pinfunction "OUT6_13") (pintype "output"))
    )
    (net (code "21") (name "Net-(IC100A-O)") (class "Default")
      (node (ref "IC100") (pin "2") (pinfunction "O_2") (pintype "output"))
      (node (ref "Q7") (pin "1") (pinfunction "GATE_1") (pintype "bidirectional"))
      (node (ref "R7") (pin "1") (pinfunction "1_1") (pintype "passive"))
    )
    (net (code "22") (name "Net-(IC100B-I)") (class "Default")
      (node (ref "IC100") (pin "3") (pinfunction "I_3") (pintype "input"))
      (node (ref "R17") (pin "1") (pinfunction "1_1") (pintype "passive"))
      (node (ref "U1") (pin "14") (pinfunction "OUT7_14") (pintype "output"))
    )
    (net (code "23") (name "Net-(IC100B-O)") (class "Default")
      (node (ref "IC100") (pin "4") (pinfunction "O_4") (pintype "output"))
      (node (ref "Q8") (pin "1") (pinfunction "GATE_1") (pintype "bidirectional"))
      (node (ref "R8") (pin "1") (pinfunction "1_1") (pintype "passive"))
    )
    (net (code "24") (name "Net-(IC100C-I)") (class "Default")
      (node (ref "IC100") (pin "5") (pinfunction "I_5") (pintype "input"))
      (node (ref "R102") (pin "2") (pinfunction "2_2") (pintype "passive"))
      (node (ref "U1") (pin "15") (pinfunction "OUT8_15") (pintype "output"))
    )
    (net (code "25") (name "Net-(IC100C-O)") (class "Default")
      (node (ref "IC100") (pin "6") (pinfunction "O_6") (pintype "output"))
      (node (ref "Q9") (pin "1") (pinfunction "GATE_1") (pintype "bidirectional"))
      (node (ref "R9") (pin "1") (pinfunction "1_1") (pintype "passive"))
    )
    (net (code "26") (name "Net-(IC100D-I)") (class "Default")
      (node (ref "IC100") (pin "9") (pinfunction "I_9") (pintype "input"))
      (node (ref "R105") (pin "2") (pinfunction "2_2") (pintype "passive"))
      (node (ref "U1") (pin "16") (pinfunction "OUT9_16") (pintype "output"))
    )
    (net (code "27") (name "Net-(IC100D-O)") (class "Default")
      (node (ref "IC100") (pin "8") (pinfunction "O_8") (pintype "output"))
      (node (ref "Q10") (pin "1") (pinfunction "GATE_1") (pintype "bidirectional"))
      (node (ref "R10") (pin "2") (pinfunction "2_2") (pintype "passive"))
    )
    (net (code "28") (name "Net-(IC100E-I)") (class "Default")
      (node (ref "IC100") (pin "11") (pinfunction "I_11") (pintype "input"))
      (node (ref "R103") (pin "2") (pinfunction "2_2") (pintype "passive"))
      (node (ref "U1") (pin "17") (pinfunction "OUT10_17") (pintype "output"))
    )
    (net (code "29") (name "Net-(IC100E-O)") (class "Default")
      (node (ref "IC100") (pin "10") (pinfunction "O_10") (pintype "output"))
      (node (ref "Q11") (pin "1") (pinfunction "GATE_1") (pintype "bidirectional"))
      (node (ref "R11") (pin "2") (pinfunction "2_2") (pintype "passive"))
    )
    (net (code "30") (name "Net-(IC100F-I)") (class "Default")
      (node (ref "IC100") (pin "13") (pinfunction "I_13") (pintype "input"))
      (node (ref "R101") (pin "2") (pinfunction "2_2") (pintype "passive"))
      (node (ref "U1") (pin "18") (pinfunction "OUT11_18") (pintype "output"))
    )
    (net (code "31") (name "Net-(IC100F-O)") (class "Default")
      (node (ref "IC100") (pin "12") (pinfunction "O_12") (pintype "output"))
      (node (ref "Q12") (pin "1") (pinfunction "GATE_1") (pintype "bidirectional"))
      (node (ref "R12") (pin "2") (pinfunction "2_2") (pintype "passive"))
    )
    (net (code "32") (name "Net-(IC101A-I)") (class "Default")
      (node (ref "IC101") (pin "1") (pinfunction "I_1") (pintype "input"))
      (node (ref "R32") (pin "1") (pinfunction "1_1") (pintype "passive"))
      (node (ref "U1") (pin "7") (pinfunction "OUT0_7") (pintype "output"))
    )
    (net (code "33") (name "Net-(IC101A-O)") (class "Default")
      (node (ref "IC101") (pin "2") (pinfunction "O_2") (pintype "output"))
      (node (ref "Q1") (pin "1") (pinfunction "GATE_1") (pintype "bidirectional"))
      (node (ref "R1") (pin "2") (pinfunction "2_2") (pintype "passive"))
    )
    (net (code "34") (name "Net-(IC101B-I)") (class "Default")
      (node (ref "IC101") (pin "3") (pinfunction "I_3") (pintype "input"))
      (node (ref "R31") (pin "1") (pinfunction "1_1") (pintype "passive"))
      (node (ref "U1") (pin "8") (pinfunction "OUT1_8") (pintype "output"))
    )
    (net (code "35") (name "Net-(IC101B-O)") (class "Default")
      (node (ref "IC101") (pin "4") (pinfunction "O_4") (pintype "output"))
      (node (ref "Q2") (pin "1") (pinfunction "GATE_1") (pintype "bidirectional"))
      (node (ref "R2") (pin "1") (pinfunction "1_1") (pintype "passive"))
    )
    (net (code "36") (name "Net-(IC101C-I)") (class "Default")
      (node (ref "IC101") (pin "5") (pinfunction "I_5") (pintype "input"))
      (node (ref "R29") (pin "1") (pinfunction "1_1") (pintype "passive"))
      (node (ref "U1") (pin "9") (pinfunction "OUT2_9") (pintype "output"))
    )
    (net (code "37") (name "Net-(IC101C-O)") (class "Default")
      (node (ref "IC101") (pin "6") (pinfunction "O_6") (pintype "output"))
      (node (ref "Q3") (pin "1") (pinfunction "GATE_1") (pintype "bidirectional"))
      (node (ref "R3") (pin "1") (pinfunction "1_1") (pintype "passive"))
    )
    (net (code "38") (name "Net-(IC101D-I)") (class "Default")
      (node (ref "IC101") (pin "9") (pinfunction "I_9") (pintype "input"))
      (node (ref "R28") (pin "1") (pinfunction "1_1") (pintype "passive"))
      (node (ref "U1") (pin "10") (pinfunction "OUT3_10") (pintype "output"))
    )
    (net (code "39") (name "Net-(IC101D-O)") (class "Default")
      (node (ref "IC101") (pin "8") (pinfunction "O_8") (pintype "output"))
      (node (ref "Q4") (pin "1") (pinfunction "GATE_1") (pintype "bidirectional"))
      (node (ref "R4") (pin "1") (pinfunction "1_1") (pintype "passive"))
    )
    (net (code "40") (name "Net-(IC101E-I)") (class "Default")
      (node (ref "IC101") (pin "11") (pinfunction "I_11") (pintype "input"))
      (node (ref "R20") (pin "1") (pinfunction "1_1") (pintype "passive"))
      (node (ref "U1") (pin "11") (pinfunction "OUT4_11") (pintype "output"))
    )
    (net (code "41") (name "Net-(IC101E-O)") (class "Default")
      (node (ref "IC101") (pin "10") (pinfunction "O_10") (pintype "output"))
      (node (ref "Q5") (pin "1") (pinfunction "GATE_1") (pintype "bidirectional"))
      (node (ref "R5") (pin "1") (pinfunction "1_1") (pintype "passive"))
    )
    (net (code "42") (name "Net-(IC101F-I)") (class "Default")
      (node (ref "IC101") (pin "13") (pinfunction "I_13") (pintype "input"))
      (node (ref "R19") (pin "1") (pinfunction "1_1") (pintype "passive"))
      (node (ref "U1") (pin "12") (pinfunction "OUT5_12") (pintype "output"))
    )
    (net (code "43") (name "Net-(IC101F-O)") (class "Default")
      (node (ref "IC101") (pin "12") (pinfunction "O_12") (pintype "output"))
      (node (ref "Q6") (pin "1") (pinfunction "GATE_1") (pintype "bidirectional"))
      (node (ref "R6") (pin "1") (pinfunction "1_1") (pintype "passive"))
    )
    (net (code "44") (name "Net-(IC102A-I)") (class "Default")
      (node (ref "IC102") (pin "1") (pinfunction "I_1") (pintype "input"))
      (node (ref "R104") (pin "2") (pinfunction "2_2") (pintype "passive"))
      (node (ref "U1") (pin "19") (pinfunction "OUT12_19") (pintype "output"))
    )
    (net (code "45") (name "Net-(IC102A-O)") (class "Default")
      (node (ref "IC102") (pin "2") (pinfunction "O_2") (pintype "output"))
      (node (ref "Q13") (pin "1") (pinfunction "GATE_1") (pintype "bidirectional"))
      (node (ref "R13") (pin "2") (pinfunction "2_2") (pintype "passive"))
    )
    (net (code "46") (name "Net-(IC102B-I)") (class "Default")
      (node (ref "IC102") (pin "3") (pinfunction "I_3") (pintype "input"))
      (node (ref "R106") (pin "2") (pinfunction "2_2") (pintype "passive"))
      (node (ref "U1") (pin "20") (pinfunction "OUT13_20") (pintype "output"))
    )
    (net (code "47") (name "Net-(IC102B-O)") (class "Default")
      (node (ref "IC102") (pin "4") (pinfunction "O_4") (pintype "output"))
      (node (ref "Q14") (pin "1") (pinfunction "GATE_1") (pintype "bidirectional"))
      (node (ref "R14") (pin "2") (pinfunction "2_2") (pintype "passive"))
    )
    (net (code "48") (name "Net-(IC102C-I)") (class "Default")
      (node (ref "IC102") (pin "5") (pinfunction "I_5") (pintype "input"))
      (node (ref "R108") (pin "2") (pinfunction "2_2") (pintype "passive"))
      (node (ref "U1") (pin "21") (pinfunction "OUT14_21") (pintype "output"))
    )
    (net (code "49") (name "Net-(IC102C-O)") (class "Default")
      (node (ref "IC102") (pin "6") (pinfunction "O_6") (pintype "output"))
      (node (ref "Q15") (pin "1") (pinfunction "GATE_1") (pintype "bidirectional"))
      (node (ref "R15") (pin "2") (pinfunction "2_2") (pintype "passive"))
    )
    (net (code "50") (name "Net-(IC102D-I)") (class "Default")
      (node (ref "IC102") (pin "9") (pinfunction "I_9") (pintype "input"))
      (node (ref "R107") (pin "2") (pinfunction "2_2") (pintype "passive"))
      (node (ref "U1") (pin "22") (pinfunction "OUT15_22") (pintype "output"))
    )
    (net (code "51") (name "Net-(IC102D-O)") (class "Default")
      (node (ref "IC102") (pin "8") (pinfunction "O_8") (pintype "output"))
      (node (ref "Q16") (pin "1") (pinfunction "GATE_1") (pintype "bidirectional"))
      (node (ref "R16") (pin "2") (pinfunction "2_2") (pintype "passive"))
    )
    (net (code "52") (name "Net-(J20-Pad1)") (class "Default")
      (node (ref "J20") (pin "1") (pinfunction "1_1") (pintype "passive"))
      (node (ref "R116") (pin "2") (pinfunction "2_2") (pintype "passive"))
    )
    (net (code "53") (name "Net-(J21-Pad1)") (class "Default")
      (node (ref "J21") (pin "1") (pinfunction "1_1") (pintype "passive"))
      (node (ref "R115") (pin "2") (pinfunction "2_2") (pintype "passive"))
    )
    (net (code "54") (name "Net-(LED1-PadC)") (class "Default")
      (node (ref "LED1") (pin "C") (pinfunction "C_C") (pintype "passive"))
      (node (ref "R43") (pin "1") (pinfunction "1_1") (pintype "passive"))
    )
    (net (code "55") (name "Net-(LED2-PadC)") (class "Default")
      (node (ref "LED2") (pin "C") (pinfunction "C_C") (pintype "passive"))
      (node (ref "R42") (pin "1") (pinfunction "1_1") (pintype "passive"))
    )
    (net (code "56") (name "Net-(Q1-DRAIN)") (class "Default")
      (node (ref "J1") (pin "1") (pinfunction "1_1") (pintype "passive"))
      (node (ref "Q1") (pin "2") (pinfunction "DRAIN_2") (pintype "bidirectional"))
    )
    (net (code "57") (name "Net-(Q2-DRAIN)") (class "Default")
      (node (ref "J2") (pin "1") (pinfunction "1_1") (pintype "passive"))
      (node (ref "Q2") (pin "2") (pinfunction "DRAIN_2") (pintype "bidirectional"))
    )
    (net (code "58") (name "Net-(Q3-DRAIN)") (class "Default")
      (node (ref "J3") (pin "1") (pinfunction "1_1") (pintype "passive"))
      (node (ref "Q3") (pin "2") (pinfunction "DRAIN_2") (pintype "bidirectional"))
    )
    (net (code "59") (name "Net-(Q4-DRAIN)") (class "Default")
      (node (ref "J4") (pin "1") (pinfunction "1_1") (pintype "passive"))
      (node (ref "Q4") (pin "2") (pinfunction "DRAIN_2") (pintype "bidirectional"))
    )
    (net (code "60") (name "Net-(Q5-DRAIN)") (class "Default")
      (node (ref "J5") (pin "1") (pinfunction "1_1") (pintype "passive"))
      (node (ref "Q5") (pin "2") (pinfunction "DRAIN_2") (pintype "bidirectional"))
    )
    (net (code "61") (name "Net-(Q6-DRAIN)") (class "Default")
      (node (ref "J6") (pin "1") (pinfunction "1_1") (pintype "passive"))
      (node (ref "Q6") (pin "2") (pinfunction "DRAIN_2") (pintype "bidirectional"))
    )
    (net (code "62") (name "Net-(Q7-DRAIN)") (class "Default")
      (node (ref "J7") (pin "1") (pinfunction "1_1") (pintype "passive"))
      (node (ref "Q7") (pin "2") (pinfunction "DRAIN_2") (pintype "bidirectional"))
    )
    (net (code "63") (name "Net-(Q8-DRAIN)") (class "Default")
      (node (ref "J8") (pin "1") (pinfunction "1_1") (pintype "passive"))
      (node (ref "Q8") (pin "2") (pinfunction "DRAIN_2") (pintype "bidirectional"))
    )
    (net (code "64") (name "Net-(Q9-DRAIN)") (class "Default")
      (node (ref "J9") (pin "1") (pinfunction "1_1") (pintype "passive"))
      (node (ref "Q9") (pin "2") (pinfunction "DRAIN_2") (pintype "bidirectional"))
    )
    (net (code "65") (name "Net-(Q10-DRAIN)") (class "Default")
      (node (ref "J10") (pin "1") (pinfunction "1_1") (pintype "passive"))
      (node (ref "Q10") (pin "2") (pinfunction "DRAIN_2") (pintype "bidirectional"))
    )
    (net (code "66") (name "Net-(Q11-DRAIN)") (class "Default")
      (node (ref "J11") (pin "1") (pinfunction "1_1") (pintype "passive"))
      (node (ref "Q11") (pin "2") (pinfunction "DRAIN_2") (pintype "bidirectional"))
    )
    (net (code "67") (name "Net-(Q12-DRAIN)") (class "Default")
      (node (ref "J12") (pin "1") (pinfunction "1_1") (pintype "passive"))
      (node (ref "Q12") (pin "2") (pinfunction "DRAIN_2") (pintype "bidirectional"))
    )
    (net (code "68") (name "Net-(Q13-DRAIN)") (class "Default")
      (node (ref "J13") (pin "1") (pinfunction "1_1") (pintype "passive"))
      (node (ref "Q13") (pin "2") (pinfunction "DRAIN_2") (pintype "bidirectional"))
    )
    (net (code "69") (name "Net-(Q14-DRAIN)") (class "Default")
      (node (ref "J14") (pin "1") (pinfunction "1_1") (pintype "passive"))
      (node (ref "Q14") (pin "2") (pinfunction "DRAIN_2") (pintype "bidirectional"))
    )
    (net (code "70") (name "Net-(Q15-DRAIN)") (class "Default")
      (node (ref "J15") (pin "1") (pinfunction "1_1") (pintype "passive"))
      (node (ref "Q15") (pin "2") (pinfunction "DRAIN_2") (pintype "bidirectional"))
    )
    (net (code "71") (name "Net-(Q16-DRAIN)") (class "Default")
      (node (ref "J16") (pin "1") (pinfunction "1_1") (pintype "passive"))
      (node (ref "Q16") (pin "2") (pinfunction "DRAIN_2") (pintype "bidirectional"))
    )
    (net (code "72") (name "Net-(Q100-S)") (class "Default")
      (node (ref "J23") (pin "2") (pinfunction "2_2") (pintype "passive"))
      (node (ref "JP2") (pin "2") (pinfunction "2_2") (pintype "passive"))
      (node (ref "Q100") (pin "2") (pinfunction "S_2") (pintype "passive"))
      (node (ref "R117") (pin "1") (pinfunction "1_1") (pintype "passive"))
    )
    (net (code "73") (name "Net-(Q101-S)") (class "Default")
      (node (ref "J22") (pin "2") (pinfunction "2_2") (pintype "passive"))
      (node (ref "JP1") (pin "1") (pinfunction "1_1") (pintype "passive"))
      (node (ref "Q101") (pin "2") (pinfunction "S_2") (pintype "passive"))
      (node (ref "R118") (pin "1") (pinfunction "1_1") (pintype "passive"))
    )
    (net (code "74") (name "Net-(U1-IREF)") (class "Default")
      (node (ref "R34") (pin "2") (pinfunction "2_2") (pintype "passive"))
      (node (ref "U1") (pin "27") (pinfunction "IREF_27") (pintype "passive"))
    )
    (net (code "75") (name "Net-(U1-SOUT)") (class "Default")
      (node (ref "SOUT") (pin "TP") (pinfunction "TP_TP") (pintype "input"))
      (node (ref "U1") (pin "24") (pinfunction "SOUT_24") (pintype "output"))
    )
    (net (code "76") (name "REG1") (class "Default")
      (node (ref "ARDUINO_NANO_V1") (pin "5") (pinfunction "A1_5") (pintype "bidirectional"))
      (node (ref "R21") (pin "2") (pinfunction "S_2") (pintype "passive"))
    )
    (net (code "77") (name "REG2") (class "Default")
      (node (ref "ARDUINO_NANO_V1") (pin "6") (pinfunction "A2_6") (pintype "bidirectional"))
      (node (ref "R22") (pin "2") (pinfunction "S_2") (pintype "passive"))
    )
    (net (code "78") (name "REG3") (class "Default")
      (node (ref "ARDUINO_NANO_V1") (pin "7") (pinfunction "A3_7") (pintype "bidirectional"))
      (node (ref "R23") (pin "2") (pinfunction "S_2") (pintype "passive"))
    )
    (net (code "79") (name "REG4") (class "Default")
      (node (ref "ARDUINO_NANO_V1") (pin "8") (pinfunction "A4_8") (pintype "bidirectional"))
      (node (ref "R24") (pin "2") (pinfunction "S_2") (pintype "passive"))
    )
    (net (code "80") (name "REG5") (class "Default")
      (node (ref "ARDUINO_NANO_V1") (pin "9") (pinfunction "A5_9") (pintype "bidirectional"))
      (node (ref "R25") (pin "2") (pinfunction "S_2") (pintype "passive"))
    )
    (net (code "81") (name "REG6") (class "Default")
      (node (ref "ARDUINO_NANO_V1") (pin "10") (pinfunction "A6_10") (pintype "bidirectional"))
      (node (ref "R26") (pin "2") (pinfunction "S_2") (pintype "passive"))
    )
    (net (code "82") (name "REG7") (class "Default")
      (node (ref "ARDUINO_NANO_V1") (pin "11") (pinfunction "A7_11") (pintype "bidirectional"))
      (node (ref "R27") (pin "2") (pinfunction "S_2") (pintype "passive"))
    )
    (net (code "83") (name "SCLK") (class "Default")
      (node (ref "ARDUINO_NANO_V1") (pin "1") (pinfunction "D13_1") (pintype "bidirectional"))
      (node (ref "SCLK") (pin "TP") (pinfunction "TP_TP") (pintype "input"))
      (node (ref "U1") (pin "4") (pinfunction "SCLK_4") (pintype "input"))
    )
    (net (code "84") (name "SENSOR_BOTTOM") (class "Default")
      (node (ref "ARDUINO_NANO_V1") (pin "25") (pinfunction "D7_25") (pintype "bidirectional"))
      (node (ref "JP2") (pin "1") (pinfunction "1_1") (pintype "passive"))
      (node (ref "Q100") (pin "3") (pinfunction "D_3") (pintype "passive"))
      (node (ref "R111") (pin "1") (pinfunction "1_1") (pintype "passive"))
    )
    (net (code "85") (name "SENSOR_TOP") (class "Default")
      (node (ref "ARDUINO_NANO_V1") (pin "26") (pinfunction "D8_26") (pintype "bidirectional"))
      (node (ref "JP1") (pin "2") (pinfunction "2_2") (pintype "passive"))
      (node (ref "Q101") (pin "3") (pinfunction "D_3") (pintype "passive"))
      (node (ref "R112") (pin "1") (pinfunction "1_1") (pintype "passive"))
    )
    (net (code "86") (name "SIN") (class "Default")
      (node (ref "ARDUINO_NANO_V1") (pin "29") (pinfunction "D11_29") (pintype "bidirectional"))
      (node (ref "U1") (pin "5") (pinfunction "SIN_5") (pintype "input"))
    )
    (net (code "87") (name "SWITCH_BOTTOM") (class "Default")
      (node (ref "ARDUINO_NANO_V1") (pin "24") (pinfunction "D6_24") (pintype "bidirectional"))
      (node (ref "C104") (pin "2") (pinfunction "2_2") (pintype "passive"))
      (node (ref "R110") (pin "1") (pinfunction "1_1") (pintype "passive"))
      (node (ref "R113") (pin "1") (pinfunction "1_1") (pintype "passive"))
    )
    (net (code "88") (name "SWITCH_TOP") (class "Default")
      (node (ref "ARDUINO_NANO_V1") (pin "23") (pinfunction "D5_23") (pintype "bidirectional"))
      (node (ref "C103") (pin "2") (pinfunction "2_2") (pintype "passive"))
      (node (ref "R109") (pin "1") (pinfunction "1_1") (pintype "passive"))
      (node (ref "R114") (pin "1") (pinfunction "1_1") (pintype "passive"))
    )
    (net (code "89") (name "XLAT") (class "Default")
      (node (ref "ARDUINO_NANO_V1") (pin "27") (pinfunction "D9_27") (pintype "bidirectional"))
      (node (ref "U1") (pin "3") (pinfunction "XLAT_3") (pintype "input"))
      (node (ref "XLAT") (pin "TP") (pinfunction "TP_TP") (pintype "input"))
    )
    (net (code "90") (name "unconnected-(ARDUINO_NANO_V1-A0-Pad4)") (class "Default")
      (node (ref "ARDUINO_NANO_V1") (pin "4") (pinfunction "A0_4") (pintype "bidirectional"))
    )
    (net (code "91") (name "unconnected-(ARDUINO_NANO_V1-AREF-Pad3)") (class "Default")
      (node (ref "ARDUINO_NANO_V1") (pin "3") (pinfunction "AREF_3") (pintype "input"))
    )
    (net (code "92") (name "unconnected-(ARDUINO_NANO_V1-RX0-Pad17)") (class "Default")
      (node (ref "ARDUINO_NANO_V1") (pin "17") (pinfunction "RX0_17") (pintype "bidirectional"))
    )
    (net (code "93") (name "unconnected-(ARDUINO_NANO_V1-TX1-Pad16)") (class "Default")
      (node (ref "ARDUINO_NANO_V1") (pin "16") (pinfunction "TX1_16") (pintype "bidirectional"))
    )
    (net (code "94") (name "unconnected-(ARDUINO_NANO_V1-~{RESET}-Pad13)") (class "Default")
      (node (ref "ARDUINO_NANO_V1") (pin "13") (pinfunction "~{RESET}_13") (pintype "input"))
    )
    (net (code "95") (name "unconnected-(ARDUINO_NANO_V1-~{RESET}-Pad18)") (class "Default")
      (node (ref "ARDUINO_NANO_V1") (pin "18") (pinfunction "~{RESET}_18") (pintype "input"))
    )
    (net (code "96") (name "unconnected-(IC102E-O-Pad10)") (class "Default")
      (node (ref "IC102") (pin "10") (pinfunction "O_10") (pintype "output"))
    )
    (net (code "97") (name "unconnected-(IC102F-O-Pad12)") (class "Default")
      (node (ref "IC102") (pin "12") (pinfunction "O_12") (pintype "output"))
    )
    (net (code "98") (name "unconnected-(R45-E-Pad3)") (class "Default")
      (node (ref "R45") (pin "3") (pinfunction "E_3") (pintype "passive"))
    )
    (net (code "99") (name "unconnected-(R46-E-Pad3)") (class "Default")
      (node (ref "R46") (pin "3") (pinfunction "E_3") (pintype "passive"))
    )
    (net (code "100") (name "unconnected-(U1-XERR-Pad23)") (class "Default")
      (node (ref "U1") (pin "23") (pinfunction "XERR_23") (pintype "output"))
    )
  )
)
